# Embedded_Chip.net
KiCad netlist of a schematic drawn in Altium Designer
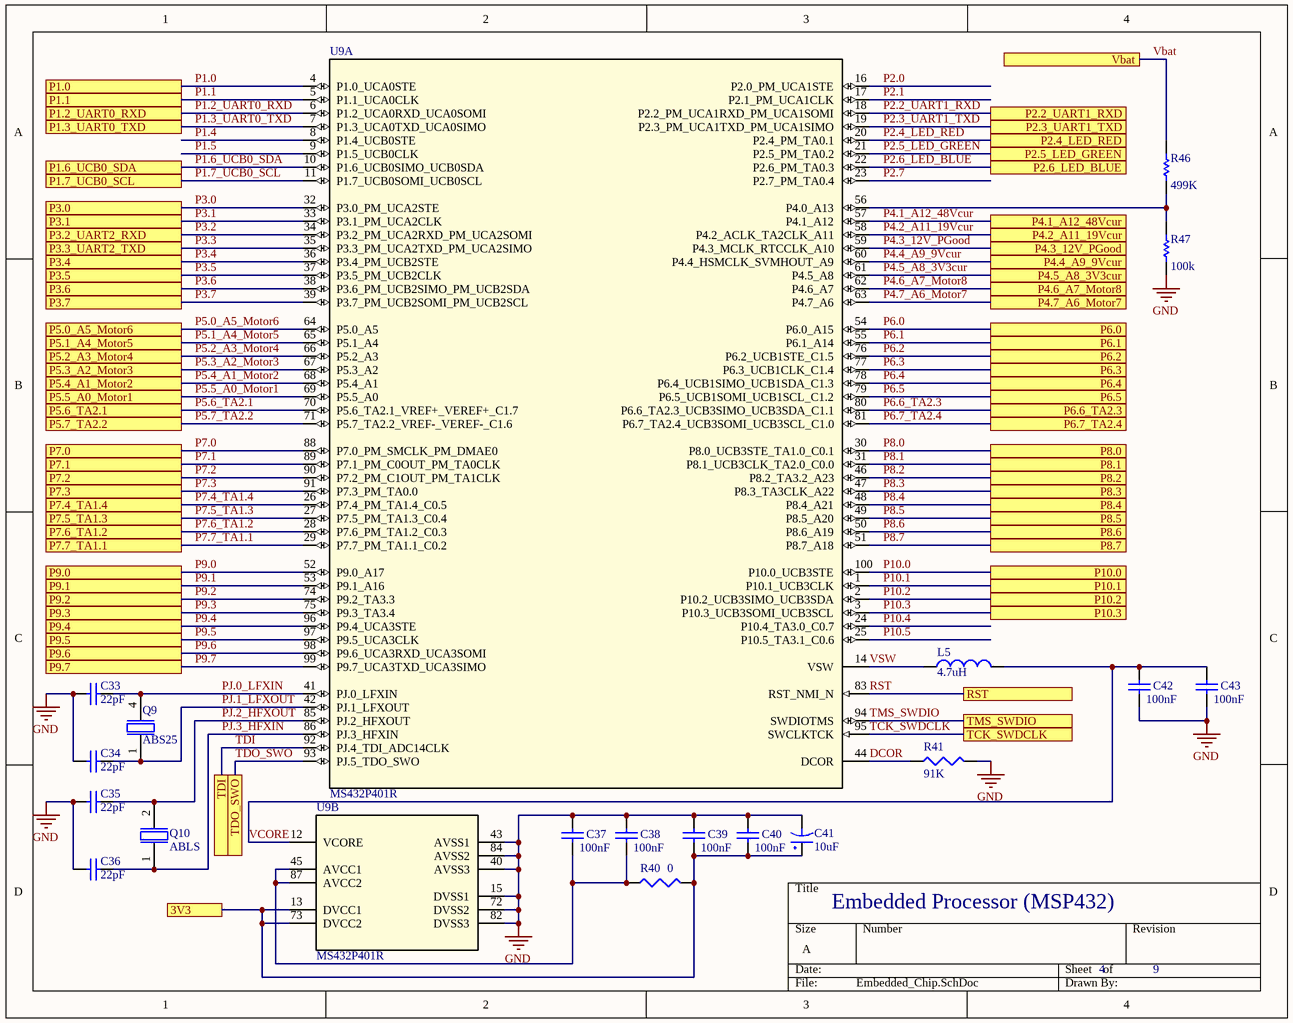
[diagram p0: Embedded_Chip.SchDoc]

(export (version "E")
  (design (tool "Eeschema 10.0.6"))
  (components
    (comp (ref "C33")
      (value "22pF")
      (footprint "C1206")
      (description "Capacitor (Semiconductor SIM Model)")
      (fields (field (name "Comment") "Cap Semi") (field (name "PUBLISHER") "Altium Limited"))
      (libsource (lib "Miscellaneous Devices") (part "Cap Semi"))
    )
    (comp (ref "C34")
      (value "22pF")
      (footprint "C1206")
      (description "Capacitor (Semiconductor SIM Model)")
      (fields (field (name "Comment") "Cap Semi") (field (name "PUBLISHER") "Altium Limited"))
      (libsource (lib "Miscellaneous Devices") (part "Cap Semi"))
    )
    (comp (ref "C35")
      (value "22pF")
      (footprint "C1206")
      (description "Capacitor (Semiconductor SIM Model)")
      (fields (field (name "Comment") "Cap Semi") (field (name "PUBLISHER") "Altium Limited"))
      (libsource (lib "Miscellaneous Devices") (part "Cap Semi"))
    )
    (comp (ref "C36")
      (value "22pF")
      (footprint "C1206")
      (description "Capacitor (Semiconductor SIM Model)")
      (fields (field (name "Comment") "Cap Semi") (field (name "PUBLISHER") "Altium Limited"))
      (libsource (lib "Miscellaneous Devices") (part "Cap Semi"))
    )
    (comp (ref "C37")
      (value "100nF")
      (footprint "C1206")
      (description "Capacitor (Semiconductor SIM Model)")
      (fields (field (name "Comment") "Cap Semi") (field (name "PUBLISHER") "Altium Limited"))
      (libsource (lib "Miscellaneous Devices") (part "Cap Semi"))
    )
    (comp (ref "C38")
      (value "100nF")
      (footprint "C1206")
      (description "Capacitor (Semiconductor SIM Model)")
      (fields (field (name "Comment") "Cap Semi") (field (name "PUBLISHER") "Altium Limited"))
      (libsource (lib "Miscellaneous Devices") (part "Cap Semi"))
    )
    (comp (ref "C39")
      (value "100nF")
      (footprint "C1206")
      (description "Capacitor (Semiconductor SIM Model)")
      (fields (field (name "Comment") "Cap Semi") (field (name "PUBLISHER") "Altium Limited"))
      (libsource (lib "Miscellaneous Devices") (part "Cap Semi"))
    )
    (comp (ref "C40")
      (value "100nF")
      (footprint "C1206")
      (description "Capacitor (Semiconductor SIM Model)")
      (fields (field (name "Comment") "Cap Semi") (field (name "PUBLISHER") "Altium Limited"))
      (libsource (lib "Miscellaneous Devices") (part "Cap Semi"))
    )
    (comp (ref "C41")
      (value "10uF")
      (footprint "UWX1C100MCL2GB")
      (description "CAP ALUM 10UF 20% 16V SMD")
      (libsource (lib "Power_Embedded_Board_Library") (part "UWX1C100MCL2GB"))
    )
    (comp (ref "C42")
      (value "100nF")
      (footprint "C1206")
      (description "Capacitor (Semiconductor SIM Model)")
      (fields (field (name "Comment") "Cap Semi") (field (name "PUBLISHER") "Altium Limited"))
      (libsource (lib "Miscellaneous Devices") (part "Cap Semi"))
    )
    (comp (ref "C43")
      (value "100nF")
      (footprint "C1206")
      (description "Capacitor (Semiconductor SIM Model)")
      (fields (field (name "Comment") "Cap Semi") (field (name "PUBLISHER") "Altium Limited"))
      (libsource (lib "Miscellaneous Devices") (part "Cap Semi"))
    )
    (comp (ref "L5")
      (value "4.7uH")
      (footprint "0806 (Metric 2016)")
      (description "Inductor")
      (fields (field (name "PUBLISHER") "Altium Limited"))
      (libsource (lib "Miscellaneous Devices") (part "Inductor"))
    )
    (comp (ref "Q9")
      (value "ABS25")
      (footprint "ABS25")
      (description "32.768 kHz Low Frequency SMD Crystal")
      (libsource (lib "Power_Embedded_Board_Library") (part "ABS25"))
    )
    (comp (ref "Q10")
      (value "ABLS")
      (footprint "ABLS")
      (description "SMD Low Profile Crystal - 3.579545 MHz to 75 MHz")
      (libsource (lib "Power_Embedded_Board_Library") (part "ABLS"))
    )
    (comp (ref "R40")
      (value "0")
      (footprint "J1-0603")
      (description "Resistor")
      (fields (field (name "Comment") "Res3") (field (name "PUBLISHER") "Altium Limited"))
      (libsource (lib "Miscellaneous Devices") (part "Res3"))
    )
    (comp (ref "R41")
      (value "91K")
      (footprint "J1-0603")
      (description "Resistor")
      (fields (field (name "Comment") "Res3") (field (name "PUBLISHER") "Altium Limited"))
      (libsource (lib "Miscellaneous Devices") (part "Res3"))
    )
    (comp (ref "R46")
      (value "499K")
      (footprint "J1-0603")
      (description "Resistor")
      (fields (field (name "Comment") "Res1") (field (name "PUBLISHER") "Altium Limited"))
      (libsource (lib "Miscellaneous Devices") (part "Res1"))
    )
    (comp (ref "R47")
      (value "100k")
      (footprint "J1-0603")
      (description "Resistor")
      (fields (field (name "Comment") "Res1") (field (name "PUBLISHER") "Altium Limited"))
      (libsource (lib "Miscellaneous Devices") (part "Res1"))
    )
    (comp (ref "U9")
      (value "MS432P401R")
      (footprint "PZ0100A_M")
      (description "SimpleLink Ultra-Low-Power 32-Bit ARM Cortex-M4F MCU With Precision ADC, 256KB Flash and 64KB RAM")
      (fields (field (name "PARTNUMBER") "XMS432P401RIPZR") (field (name "MANUFACTURER") "Texas Instruments"))
      (libsource (lib "Power_Embedded_Board_Library") (part "MS432P401R-IPZR"))
    )
  )
  (nets
    (net (code "1") (name "/3V3") (class "Default")
      (node (ref "C39") (pin "1") (pinfunction "1_1") (pintype "passive"))
      (node (ref "C40") (pin "1") (pinfunction "1_1") (pintype "passive"))
      (node (ref "C41") (pin "1") (pinfunction "1_1") (pintype "passive"))
      (node (ref "R40") (pin "2") (pinfunction "2_2") (pintype "passive"))
      (node (ref "U9") (pin "13") (pinfunction "DVCC1_13") (pintype "power_in"))
      (node (ref "U9") (pin "73") (pinfunction "DVCC2_73") (pintype "power_in"))
    )
    (net (code "2") (name "/DCOR") (class "Default")
      (node (ref "R41") (pin "1") (pinfunction "1_1") (pintype "passive"))
      (node (ref "U9") (pin "44") (pinfunction "DCOR_44") (pintype "passive"))
    )
    (net (code "3") (name "/P1.0") (class "Default")
      (node (ref "U9") (pin "4") (pinfunction "P1.0_UCA0STE_4") (pintype "bidirectional"))
    )
    (net (code "4") (name "/P1.1") (class "Default")
      (node (ref "U9") (pin "5") (pinfunction "P1.1_UCA0CLK_5") (pintype "bidirectional"))
    )
    (net (code "5") (name "/P1.2_UART0_RXD") (class "Default")
      (node (ref "U9") (pin "6") (pinfunction "P1.2_UCA0RXD_UCA0SOMI_6") (pintype "bidirectional"))
    )
    (net (code "6") (name "/P1.3_UART0_TXD") (class "Default")
      (node (ref "U9") (pin "7") (pinfunction "P1.3_UCA0TXD_UCA0SIMO_7") (pintype "bidirectional"))
    )
    (net (code "7") (name "/P1.4") (class "Default")
      (node (ref "U9") (pin "8") (pinfunction "P1.4_UCB0STE_8") (pintype "bidirectional"))
    )
    (net (code "8") (name "/P1.5") (class "Default")
      (node (ref "U9") (pin "9") (pinfunction "P1.5_UCB0CLK_9") (pintype "bidirectional"))
    )
    (net (code "9") (name "/P1.6_UCB0_SDA") (class "Default")
      (node (ref "U9") (pin "10") (pinfunction "P1.6_UCB0SIMO_UCB0SDA_10") (pintype "bidirectional"))
    )
    (net (code "10") (name "/P1.7_UCB0_SCL") (class "Default")
      (node (ref "U9") (pin "11") (pinfunction "P1.7_UCB0SOMI_UCB0SCL_11") (pintype "bidirectional"))
    )
    (net (code "11") (name "/P2.0") (class "Default")
      (node (ref "U9") (pin "16") (pinfunction "P2.0_PM_UCA1STE_16") (pintype "bidirectional"))
    )
    (net (code "12") (name "/P2.1") (class "Default")
      (node (ref "U9") (pin "17") (pinfunction "P2.1_PM_UCA1CLK_17") (pintype "bidirectional"))
    )
    (net (code "13") (name "/P2.2_UART1_RXD") (class "Default")
      (node (ref "U9") (pin "18") (pinfunction "P2.2_PM_UCA1RXD_PM_UCA1SOMI_18") (pintype "bidirectional"))
    )
    (net (code "14") (name "/P2.3_UART1_TXD") (class "Default")
      (node (ref "U9") (pin "19") (pinfunction "P2.3_PM_UCA1TXD_PM_UCA1SIMO_19") (pintype "bidirectional"))
    )
    (net (code "15") (name "/P2.4_LED_RED") (class "Default")
      (node (ref "U9") (pin "20") (pinfunction "P2.4_PM_TA0.1_20") (pintype "bidirectional"))
    )
    (net (code "16") (name "/P2.5_LED_GREEN") (class "Default")
      (node (ref "U9") (pin "21") (pinfunction "P2.5_PM_TA0.2_21") (pintype "bidirectional"))
    )
    (net (code "17") (name "/P2.6_LED_BLUE") (class "Default")
      (node (ref "U9") (pin "22") (pinfunction "P2.6_PM_TA0.3_22") (pintype "bidirectional"))
    )
    (net (code "18") (name "/P2.7") (class "Default")
      (node (ref "U9") (pin "23") (pinfunction "P2.7_PM_TA0.4_23") (pintype "bidirectional"))
    )
    (net (code "19") (name "/P3.0") (class "Default")
      (node (ref "U9") (pin "32") (pinfunction "P3.0_PM_UCA2STE_32") (pintype "bidirectional"))
    )
    (net (code "20") (name "/P3.1") (class "Default")
      (node (ref "U9") (pin "33") (pinfunction "P3.1_PM_UCA2CLK_33") (pintype "bidirectional"))
    )
    (net (code "21") (name "/P3.2") (class "Default")
      (node (ref "U9") (pin "34") (pinfunction "P3.2_PM_UCA2RXD_PM_UCA2SOMI_34") (pintype "bidirectional"))
    )
    (net (code "22") (name "/P3.3") (class "Default")
      (node (ref "U9") (pin "35") (pinfunction "P3.3_PM_UCA2TXD_PM_UCA2SIMO_35") (pintype "bidirectional"))
    )
    (net (code "23") (name "/P3.4") (class "Default")
      (node (ref "U9") (pin "36") (pinfunction "P3.4_PM_UCB2STE_36") (pintype "bidirectional"))
    )
    (net (code "24") (name "/P3.5") (class "Default")
      (node (ref "U9") (pin "37") (pinfunction "P3.5_PM_UCB2CLK_37") (pintype "bidirectional"))
    )
    (net (code "25") (name "/P3.6") (class "Default")
      (node (ref "U9") (pin "38") (pinfunction "P3.6_PM_UCB2SIMO_PM_UCB2SDA_38") (pintype "bidirectional"))
    )
    (net (code "26") (name "/P3.7") (class "Default")
      (node (ref "U9") (pin "39") (pinfunction "P3.7_PM_UCB2SOMI_PM_UCB2SCL_39") (pintype "bidirectional"))
    )
    (net (code "27") (name "/P4.1_A12_48Vcur") (class "Default")
      (node (ref "U9") (pin "57") (pinfunction "P4.1_A12_57") (pintype "bidirectional"))
    )
    (net (code "28") (name "/P4.2_A11_19Vcur") (class "Default")
      (node (ref "U9") (pin "58") (pinfunction "P4.2_ACLK_TA2CLK_A11_58") (pintype "bidirectional"))
    )
    (net (code "29") (name "/P4.3_12V_PGood") (class "Default")
      (node (ref "U9") (pin "59") (pinfunction "P4.3_MCLK_RTCCLK_A10_59") (pintype "bidirectional"))
    )
    (net (code "30") (name "/P4.4_A9_9Vcur") (class "Default")
      (node (ref "U9") (pin "60") (pinfunction "P4.4_HSMCLK_SVMHOUT_A9_60") (pintype "bidirectional"))
    )
    (net (code "31") (name "/P4.5_A8_3V3cur") (class "Default")
      (node (ref "U9") (pin "61") (pinfunction "P4.5_A8_61") (pintype "bidirectional"))
    )
    (net (code "32") (name "/P4.6_A7_Motor8") (class "Default")
      (node (ref "U9") (pin "62") (pinfunction "P4.6_A7_62") (pintype "bidirectional"))
    )
    (net (code "33") (name "/P4.7_A6_Motor7") (class "Default")
      (node (ref "U9") (pin "63") (pinfunction "P4.7_A6_63") (pintype "bidirectional"))
    )
    (net (code "34") (name "/P5.0_A5_Motor6") (class "Default")
      (node (ref "U9") (pin "64") (pinfunction "P5.0_A5_64") (pintype "bidirectional"))
    )
    (net (code "35") (name "/P5.1_A4_Motor5") (class "Default")
      (node (ref "U9") (pin "65") (pinfunction "P5.1_A4_65") (pintype "bidirectional"))
    )
    (net (code "36") (name "/P5.2_A3_Motor4") (class "Default")
      (node (ref "U9") (pin "66") (pinfunction "P5.2_A3_66") (pintype "bidirectional"))
    )
    (net (code "37") (name "/P5.3_A2_Motor3") (class "Default")
      (node (ref "U9") (pin "67") (pinfunction "P5.3_A2_67") (pintype "bidirectional"))
    )
    (net (code "38") (name "/P5.4_A1_Motor2") (class "Default")
      (node (ref "U9") (pin "68") (pinfunction "P5.4_A1_68") (pintype "bidirectional"))
    )
    (net (code "39") (name "/P5.5_A0_Motor1") (class "Default")
      (node (ref "U9") (pin "69") (pinfunction "P5.5_A0_69") (pintype "bidirectional"))
    )
    (net (code "40") (name "/P5.6_TA2.1") (class "Default")
      (node (ref "U9") (pin "70") (pinfunction "P5.6_TA2.1_VREF+_VEREF+_C1.7_70") (pintype "bidirectional"))
    )
    (net (code "41") (name "/P5.7_TA2.2") (class "Default")
      (node (ref "U9") (pin "71") (pinfunction "P5.7_TA2.2_VREF-_VEREF-_C1.6_71") (pintype "bidirectional"))
    )
    (net (code "42") (name "/P6.0") (class "Default")
      (node (ref "U9") (pin "54") (pinfunction "P6.0_A15_54") (pintype "bidirectional"))
    )
    (net (code "43") (name "/P6.1") (class "Default")
      (node (ref "U9") (pin "55") (pinfunction "P6.1_A14_55") (pintype "bidirectional"))
    )
    (net (code "44") (name "/P6.2") (class "Default")
      (node (ref "U9") (pin "76") (pinfunction "P6.2_UCB1STE_C1.5_76") (pintype "bidirectional"))
    )
    (net (code "45") (name "/P6.3") (class "Default")
      (node (ref "U9") (pin "77") (pinfunction "P6.3_UCB1CLK_C1.4_77") (pintype "bidirectional"))
    )
    (net (code "46") (name "/P6.4") (class "Default")
      (node (ref "U9") (pin "78") (pinfunction "P6.4_UCB1SIMO_UCB1SDA_C1.3_78") (pintype "bidirectional"))
    )
    (net (code "47") (name "/P6.5") (class "Default")
      (node (ref "U9") (pin "79") (pinfunction "P6.5_UCB1SOMI_UCB1SCL_C1.2_79") (pintype "bidirectional"))
    )
    (net (code "48") (name "/P6.6_TA2.3") (class "Default")
      (node (ref "U9") (pin "80") (pinfunction "P6.6_TA2.3_UCB3SIMO_UCB3SDA_C1.1_80") (pintype "bidirectional"))
    )
    (net (code "49") (name "/P6.7_TA2.4") (class "Default")
      (node (ref "U9") (pin "81") (pinfunction "P6.7_TA2.4_UCB3SOMI_UCB3SCL_C1.0_81") (pintype "bidirectional"))
    )
    (net (code "50") (name "/P7.0") (class "Default")
      (node (ref "U9") (pin "88") (pinfunction "P7.0_PM_SMCLK_PM_DMAE0_88") (pintype "bidirectional"))
    )
    (net (code "51") (name "/P7.1") (class "Default")
      (node (ref "U9") (pin "89") (pinfunction "P7.1_PM_C0OUT_PM_TA0CLK_89") (pintype "bidirectional"))
    )
    (net (code "52") (name "/P7.2") (class "Default")
      (node (ref "U9") (pin "90") (pinfunction "P7.2_PM_C1OUT_PM_TA1CLK_90") (pintype "bidirectional"))
    )
    (net (code "53") (name "/P7.3") (class "Default")
      (node (ref "U9") (pin "91") (pinfunction "P7.3_PM_TA0.0_91") (pintype "bidirectional"))
    )
    (net (code "54") (name "/P7.4_TA1.4") (class "Default")
      (node (ref "U9") (pin "26") (pinfunction "P7.4_PM_TA1.4_C0.5_26") (pintype "bidirectional"))
    )
    (net (code "55") (name "/P7.5_TA1.3") (class "Default")
      (node (ref "U9") (pin "27") (pinfunction "P7.5_PM_TA1.3_C0.4_27") (pintype "bidirectional"))
    )
    (net (code "56") (name "/P7.6_TA1.2") (class "Default")
      (node (ref "U9") (pin "28") (pinfunction "P7.6_PM_TA1.2_C0.3_28") (pintype "bidirectional"))
    )
    (net (code "57") (name "/P7.7_TA1.1") (class "Default")
      (node (ref "U9") (pin "29") (pinfunction "P7.7_PM_TA1.1_C0.2_29") (pintype "bidirectional"))
    )
    (net (code "58") (name "/P8.0") (class "Default")
      (node (ref "U9") (pin "30") (pinfunction "P8.0_UCB3STE_TA1.0_C0.1_30") (pintype "bidirectional"))
    )
    (net (code "59") (name "/P8.1") (class "Default")
      (node (ref "U9") (pin "31") (pinfunction "P8.1_UCB3CLK_TA2.0_C0.0_31") (pintype "bidirectional"))
    )
    (net (code "60") (name "/P8.2") (class "Default")
      (node (ref "U9") (pin "46") (pinfunction "P8.2_TA3.2_A23_46") (pintype "bidirectional"))
    )
    (net (code "61") (name "/P8.3") (class "Default")
      (node (ref "U9") (pin "47") (pinfunction "P8.3_TA3CLK_A22_47") (pintype "bidirectional"))
    )
    (net (code "62") (name "/P8.4") (class "Default")
      (node (ref "U9") (pin "48") (pinfunction "P8.4_A21_48") (pintype "bidirectional"))
    )
    (net (code "63") (name "/P8.5") (class "Default")
      (node (ref "U9") (pin "49") (pinfunction "P8.5_A20_49") (pintype "bidirectional"))
    )
    (net (code "64") (name "/P8.6") (class "Default")
      (node (ref "U9") (pin "50") (pinfunction "P8.6_A19_50") (pintype "bidirectional"))
    )
    (net (code "65") (name "/P8.7") (class "Default")
      (node (ref "U9") (pin "51") (pinfunction "P8.7_A18_51") (pintype "bidirectional"))
    )
    (net (code "66") (name "/P9.0") (class "Default")
      (node (ref "U9") (pin "52") (pinfunction "P9.0_A17_52") (pintype "bidirectional"))
    )
    (net (code "67") (name "/P9.1") (class "Default")
      (node (ref "U9") (pin "53") (pinfunction "P9.1_A16_53") (pintype "bidirectional"))
    )
    (net (code "68") (name "/P9.2") (class "Default")
      (node (ref "U9") (pin "74") (pinfunction "P9.2_TA3.3_74") (pintype "bidirectional"))
    )
    (net (code "69") (name "/P9.3") (class "Default")
      (node (ref "U9") (pin "75") (pinfunction "P9.3_TA3.4_75") (pintype "bidirectional"))
    )
    (net (code "70") (name "/P9.4") (class "Default")
      (node (ref "U9") (pin "96") (pinfunction "P9.4_UCA3STE_96") (pintype "bidirectional"))
    )
    (net (code "71") (name "/P9.5") (class "Default")
      (node (ref "U9") (pin "97") (pinfunction "P9.5_UCA3CLK_97") (pintype "bidirectional"))
    )
    (net (code "72") (name "/P9.6") (class "Default")
      (node (ref "U9") (pin "98") (pinfunction "P9.6_UCA3RXD_UCA3SOMI_98") (pintype "bidirectional"))
    )
    (net (code "73") (name "/P9.7") (class "Default")
      (node (ref "U9") (pin "99") (pinfunction "P9.7_UCA3TXD_UCA3SIMO_99") (pintype "bidirectional"))
    )
    (net (code "74") (name "/P10.0") (class "Default")
      (node (ref "U9") (pin "100") (pinfunction "P10.0_UCB3STE_100") (pintype "bidirectional"))
    )
    (net (code "75") (name "/P10.1") (class "Default")
      (node (ref "U9") (pin "1") (pinfunction "P10.1_UCB3CLK_1") (pintype "bidirectional"))
    )
    (net (code "76") (name "/P10.2") (class "Default")
      (node (ref "U9") (pin "2") (pinfunction "P10.2_UCB3SIMO_UCB3SDA_2") (pintype "bidirectional"))
    )
    (net (code "77") (name "/P10.3") (class "Default")
      (node (ref "U9") (pin "3") (pinfunction "P10.3_UCB3SOMI_UCB3SCL_3") (pintype "bidirectional"))
    )
    (net (code "78") (name "/P10.4") (class "Default")
      (node (ref "U9") (pin "24") (pinfunction "P10.4_TA3.0_C0.7_24") (pintype "bidirectional"))
    )
    (net (code "79") (name "/P10.5") (class "Default")
      (node (ref "U9") (pin "25") (pinfunction "P10.5_TA3.1_C0.6_25") (pintype "bidirectional"))
    )
    (net (code "80") (name "/PJ.0_LFXIN") (class "Default")
      (node (ref "C33") (pin "2") (pinfunction "2_2") (pintype "passive"))
      (node (ref "Q9") (pin "4") (pinfunction "4_4") (pintype "passive"))
      (node (ref "U9") (pin "41") (pinfunction "PJ.0_LFXIN_41") (pintype "bidirectional"))
    )
    (net (code "81") (name "/PJ.1_LFXOUT") (class "Default")
      (node (ref "C34") (pin "2") (pinfunction "2_2") (pintype "passive"))
      (node (ref "Q9") (pin "1") (pinfunction "1_1") (pintype "passive"))
      (node (ref "U9") (pin "42") (pinfunction "PJ.1_LFXOUT_42") (pintype "bidirectional"))
    )
    (net (code "82") (name "/PJ.2_HFXOUT") (class "Default")
      (node (ref "C35") (pin "2") (pinfunction "2_2") (pintype "passive"))
      (node (ref "Q10") (pin "2") (pinfunction "2_2") (pintype "passive"))
      (node (ref "U9") (pin "85") (pinfunction "PJ.2_HFXOUT_85") (pintype "bidirectional"))
    )
    (net (code "83") (name "/PJ.3_HFXIN") (class "Default")
      (node (ref "C36") (pin "2") (pinfunction "2_2") (pintype "passive"))
      (node (ref "Q10") (pin "1") (pinfunction "1_1") (pintype "passive"))
      (node (ref "U9") (pin "86") (pinfunction "PJ.3_HFXIN_86") (pintype "bidirectional"))
    )
    (net (code "84") (name "/RST") (class "Default")
      (node (ref "U9") (pin "83") (pinfunction "RST_NMI_N_83") (pintype "input"))
    )
    (net (code "85") (name "/TCK_SWDCLK") (class "Default")
      (node (ref "U9") (pin "95") (pinfunction "SWCLKTCK_95") (pintype "input"))
    )
    (net (code "86") (name "/TDI") (class "Default")
      (node (ref "U9") (pin "92") (pinfunction "PJ.4_TDI_ADC14CLK_92") (pintype "bidirectional"))
    )
    (net (code "87") (name "/TDO_SWO") (class "Default")
      (node (ref "U9") (pin "93") (pinfunction "PJ.5_TDO_SWO_93") (pintype "bidirectional"))
    )
    (net (code "88") (name "/TMS_SWDIO") (class "Default")
      (node (ref "U9") (pin "94") (pinfunction "SWDIOTMS_94") (pintype "bidirectional"))
    )
    (net (code "89") (name "/VCORE") (class "Default")
      (node (ref "C42") (pin "2") (pinfunction "2_2") (pintype "passive"))
      (node (ref "C43") (pin "2") (pinfunction "2_2") (pintype "passive"))
      (node (ref "L5") (pin "2") (pinfunction "2_2") (pintype "passive"))
      (node (ref "U9") (pin "12") (pinfunction "VCORE_12") (pintype "power_in"))
    )
    (net (code "90") (name "/VSW") (class "Default")
      (node (ref "L5") (pin "1") (pinfunction "1_1") (pintype "passive"))
      (node (ref "U9") (pin "14") (pinfunction "VSW_14") (pintype "passive"))
    )
    (net (code "91") (name "/Vbat") (class "Default")
      (node (ref "R46") (pin "2") (pinfunction "2_2") (pintype "passive"))
    )
    (net (code "92") (name "GND") (class "Default")
      (node (ref "C33") (pin "1") (pinfunction "1_1") (pintype "passive"))
      (node (ref "C34") (pin "1") (pinfunction "1_1") (pintype "passive"))
      (node (ref "C35") (pin "1") (pinfunction "1_1") (pintype "passive"))
      (node (ref "C36") (pin "1") (pinfunction "1_1") (pintype "passive"))
      (node (ref "C37") (pin "2") (pinfunction "2_2") (pintype "passive"))
      (node (ref "C38") (pin "2") (pinfunction "2_2") (pintype "passive"))
      (node (ref "C39") (pin "2") (pinfunction "2_2") (pintype "passive"))
      (node (ref "C40") (pin "2") (pinfunction "2_2") (pintype "passive"))
      (node (ref "C41") (pin "2") (pinfunction "2_2") (pintype "passive"))
      (node (ref "C42") (pin "1") (pinfunction "1_1") (pintype "passive"))
      (node (ref "C43") (pin "1") (pinfunction "1_1") (pintype "passive"))
      (node (ref "R41") (pin "2") (pinfunction "2_2") (pintype "passive"))
      (node (ref "R47") (pin "1") (pinfunction "1_1") (pintype "passive"))
      (node (ref "U9") (pin "15") (pinfunction "DVSS1_15") (pintype "power_in"))
      (node (ref "U9") (pin "40") (pinfunction "AVSS3_40") (pintype "power_in"))
      (node (ref "U9") (pin "43") (pinfunction "AVSS1_43") (pintype "power_in"))
      (node (ref "U9") (pin "72") (pinfunction "DVSS2_72") (pintype "power_in"))
      (node (ref "U9") (pin "82") (pinfunction "DVSS3_82") (pintype "power_in"))
      (node (ref "U9") (pin "84") (pinfunction "AVSS2_84") (pintype "power_in"))
    )
    (net (code "93") (name "Net-(U9A-P4.0_A13)") (class "Default")
      (node (ref "R46") (pin "1") (pinfunction "1_1") (pintype "passive"))
      (node (ref "R47") (pin "2") (pinfunction "2_2") (pintype "passive"))
      (node (ref "U9") (pin "56") (pinfunction "P4.0_A13_56") (pintype "bidirectional"))
    )
    (net (code "94") (name "Net-(U9B-AVCC1)") (class "Default")
      (node (ref "C37") (pin "1") (pinfunction "1_1") (pintype "passive"))
      (node (ref "C38") (pin "1") (pinfunction "1_1") (pintype "passive"))
      (node (ref "R40") (pin "1") (pinfunction "1_1") (pintype "passive"))
      (node (ref "U9") (pin "45") (pinfunction "AVCC1_45") (pintype "power_in"))
      (node (ref "U9") (pin "87") (pinfunction "AVCC2_87") (pintype "power_in"))
    )
  )
)
